# SDT_Neon_Predradnik.net
KiCad netlist of a schematic drawn in EAGLE
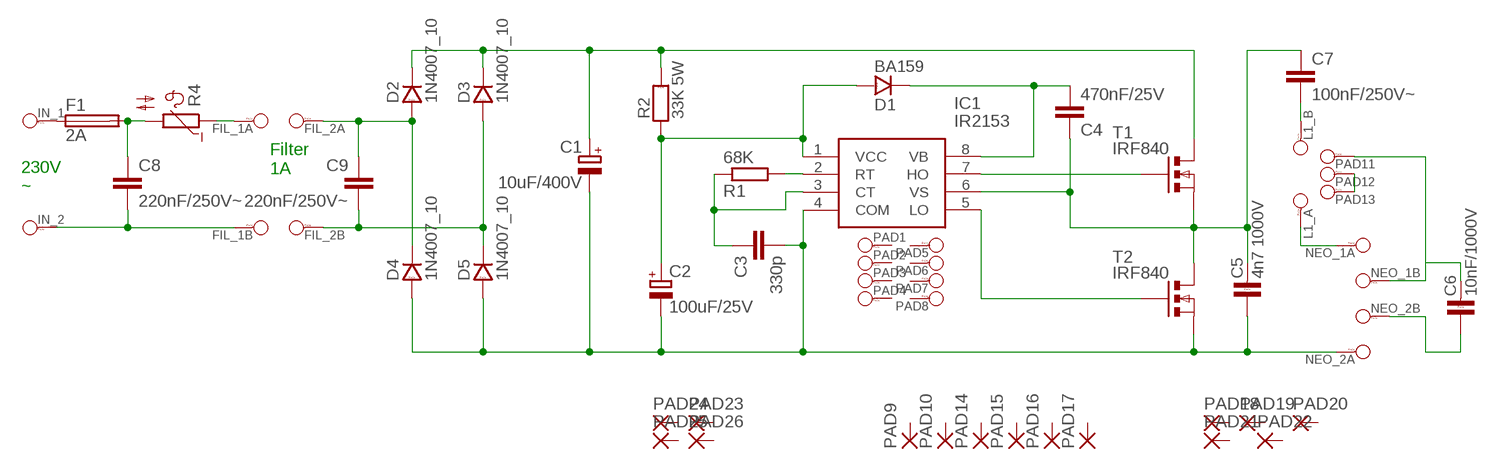
[diagram p0: schematic, sheet 1]

(export (version "E")
  (design (tool "Eeschema 10.0.6"))
  (components
    (comp (ref "C1")
      (value "10uF/400V")
      (footprint "eagle-import:ELEKTROLITICKY_RM5-10")
      (libsource (lib "eagle-import") (part "ELEKTROLITICKYRM5-10"))
    )
    (comp (ref "C2")
      (value "100uF/25V")
      (footprint "eagle-import:ELEKTROLITICKY_RM2,5-6,3")
      (libsource (lib "eagle-import") (part "ELEKTROLITICKYRM2,5-6,3"))
    )
    (comp (ref "C3")
      (value "330p")
      (footprint "eagle-import:KERAMICKY_RM5")
      (libsource (lib "eagle-import") (part "KERAMICKYRM5"))
    )
    (comp (ref "C4")
      (value "470nF/25V")
      (footprint "eagle-import:FOLIOVY_RM5_3,5-7,2")
      (libsource (lib "eagle-import") (part "FOLIOVYRM5/3,5-7,2"))
    )
    (comp (ref "C5")
      (value "4n7 1000V")
      (footprint "eagle-import:C-7,5")
      (libsource (lib "eagle-import") (part "C-KERAMIK_7,5"))
    )
    (comp (ref "C6")
      (value "10nF/1000V")
      (footprint "eagle-import:C-10")
      (libsource (lib "eagle-import") (part "C-KERAMIK_10"))
    )
    (comp (ref "C7")
      (value "100nF/250V~")
      (footprint "eagle-import:FOLIOVY_RM15_5-18")
      (libsource (lib "eagle-import") (part "FOLIOVYRM15/5-18"))
    )
    (comp (ref "C8")
      (value "220nF/250V~")
      (footprint "eagle-import:FOLIOVY_RM15_5-18")
      (libsource (lib "eagle-import") (part "FOLIOVYRM15/5-18"))
    )
    (comp (ref "C9")
      (value "220nF/250V~")
      (footprint "eagle-import:FOLIOVY_RM15_5-18")
      (libsource (lib "eagle-import") (part "FOLIOVYRM15/5-18"))
    )
    (comp (ref "D1")
      (value "BA159")
      (footprint "eagle-import:D-10")
      (libsource (lib "eagle-import") (part "BA159"))
    )
    (comp (ref "D2")
      (value "1N4007_10")
      (footprint "eagle-import:D-10")
      (libsource (lib "eagle-import") (part "1N4007_10"))
    )
    (comp (ref "D3")
      (value "1N4007_10")
      (footprint "eagle-import:D-10")
      (libsource (lib "eagle-import") (part "1N4007_10"))
    )
    (comp (ref "D4")
      (value "1N4007_10")
      (footprint "eagle-import:D-10")
      (libsource (lib "eagle-import") (part "1N4007_10"))
    )
    (comp (ref "D5")
      (value "1N4007_10")
      (footprint "eagle-import:D-10")
      (libsource (lib "eagle-import") (part "1N4007_10"))
    )
    (comp (ref "F1")
      (value "2A")
      (footprint "eagle-import:TE5")
      (libsource (lib "eagle-import") (part "FUSETE5"))
    )
    (comp (ref "FIL_1A")
      (value "PAD_1---")
      (footprint "eagle-import:PAD_1---")
      (libsource (lib "eagle-import") (part "PAD_1---"))
    )
    (comp (ref "FIL_1B")
      (value "PAD_1---")
      (footprint "eagle-import:PAD_1---")
      (libsource (lib "eagle-import") (part "PAD_1---"))
    )
    (comp (ref "FIL_2A")
      (value "PAD_1---")
      (footprint "eagle-import:PAD_1---")
      (libsource (lib "eagle-import") (part "PAD_1---"))
    )
    (comp (ref "FIL_2B")
      (value "PAD_1---")
      (footprint "eagle-import:PAD_1---")
      (libsource (lib "eagle-import") (part "PAD_1---"))
    )
    (comp (ref "IC1")
      (value "IR2153")
      (footprint "eagle-import:DIP762W56P254L988H533Q8N")
      (fields
        (field (name "MANUFACTURER_PART_NUMBER") "IR2153PBF")
        (field (name "MOUSER_PART_NUMBER") "942-IR2153PBF")
      )
      (libsource (lib "eagle-import") (part "IR2153PBF"))
    )
    (comp (ref "IN_1")
      (value "IN_~_1")
      (footprint "eagle-import:PAD_1---")
      (libsource (lib "eagle-import") (part "PAD_1---"))
    )
    (comp (ref "IN_2")
      (value "IN_~_1")
      (footprint "eagle-import:PAD_1---")
      (libsource (lib "eagle-import") (part "PAD_1---"))
    )
    (comp (ref "L1_A")
      (value "PAD_1---")
      (footprint "eagle-import:PAD_1---")
      (libsource (lib "eagle-import") (part "PAD_1---"))
    )
    (comp (ref "L1_B")
      (value "PAD_1---")
      (footprint "eagle-import:PAD_1---")
      (libsource (lib "eagle-import") (part "PAD_1---"))
    )
    (comp (ref "NEO_1A")
      (value "PAD_1---")
      (footprint "eagle-import:PAD_1---")
      (libsource (lib "eagle-import") (part "PAD_1---"))
    )
    (comp (ref "NEO_1B")
      (value "PAD_1---")
      (footprint "eagle-import:PAD_1---")
      (libsource (lib "eagle-import") (part "PAD_1---"))
    )
    (comp (ref "NEO_2A")
      (value "PAD_1---")
      (footprint "eagle-import:PAD_1---")
      (libsource (lib "eagle-import") (part "PAD_1---"))
    )
    (comp (ref "NEO_2B")
      (value "PAD_1---")
      (footprint "eagle-import:PAD_1---")
      (libsource (lib "eagle-import") (part "PAD_1---"))
    )
    (comp (ref "PAD1")
      (value "PAD_1---")
      (footprint "eagle-import:PAD_1---")
      (libsource (lib "eagle-import") (part "PAD_1---"))
    )
    (comp (ref "PAD2")
      (value "PAD_1---")
      (footprint "eagle-import:PAD_1---")
      (libsource (lib "eagle-import") (part "PAD_1---"))
    )
    (comp (ref "PAD3")
      (value "PAD_1---")
      (footprint "eagle-import:PAD_1---")
      (libsource (lib "eagle-import") (part "PAD_1---"))
    )
    (comp (ref "PAD4")
      (value "PAD_1---")
      (footprint "eagle-import:PAD_1---")
      (libsource (lib "eagle-import") (part "PAD_1---"))
    )
    (comp (ref "PAD5")
      (value "PAD_1---")
      (footprint "eagle-import:PAD_1---")
      (libsource (lib "eagle-import") (part "PAD_1---"))
    )
    (comp (ref "PAD6")
      (value "PAD_1---")
      (footprint "eagle-import:PAD_1---")
      (libsource (lib "eagle-import") (part "PAD_1---"))
    )
    (comp (ref "PAD7")
      (value "PAD_1---")
      (footprint "eagle-import:PAD_1---")
      (libsource (lib "eagle-import") (part "PAD_1---"))
    )
    (comp (ref "PAD8")
      (value "PAD_1---")
      (footprint "eagle-import:PAD_1---")
      (libsource (lib "eagle-import") (part "PAD_1---"))
    )
    (comp (ref "PAD9")
      (value "3,81/1,3")
      (footprint "eagle-import:3,81_1,3")
      (libsource (lib "eagle-import") (part "3,81/1,3"))
    )
    (comp (ref "PAD10")
      (value "3,81/1,3")
      (footprint "eagle-import:3,81_1,3")
      (libsource (lib "eagle-import") (part "3,81/1,3"))
    )
    (comp (ref "PAD11")
      (value "PAD_1---")
      (footprint "eagle-import:PAD_1---")
      (libsource (lib "eagle-import") (part "PAD_1---"))
    )
    (comp (ref "PAD12")
      (value "PAD_1---")
      (footprint "eagle-import:PAD_1---")
      (libsource (lib "eagle-import") (part "PAD_1---"))
    )
    (comp (ref "PAD13")
      (value "PAD_1---")
      (footprint "eagle-import:PAD_1---")
      (libsource (lib "eagle-import") (part "PAD_1---"))
    )
    (comp (ref "PAD14")
      (value "3,81/1,3")
      (footprint "eagle-import:3,81_1,3")
      (libsource (lib "eagle-import") (part "3,81/1,3"))
    )
    (comp (ref "PAD15")
      (value "3,81/1,3")
      (footprint "eagle-import:3,81_1,3")
      (libsource (lib "eagle-import") (part "3,81/1,3"))
    )
    (comp (ref "PAD16")
      (value "3,81/1,3")
      (footprint "eagle-import:3,81_1,3")
      (libsource (lib "eagle-import") (part "3,81/1,3"))
    )
    (comp (ref "PAD17")
      (value "3,81/1,3")
      (footprint "eagle-import:3,81_1,3")
      (libsource (lib "eagle-import") (part "3,81/1,3"))
    )
    (comp (ref "PAD18")
      (value "2,54/1,1")
      (footprint "eagle-import:2,54_1,1")
      (libsource (lib "eagle-import") (part "2,54/1,1"))
    )
    (comp (ref "PAD19")
      (value "2,54/1,1")
      (footprint "eagle-import:2,54_1,1")
      (libsource (lib "eagle-import") (part "2,54/1,1"))
    )
    (comp (ref "PAD20")
      (value "2,54/1,1")
      (footprint "eagle-import:2,54_1,1")
      (libsource (lib "eagle-import") (part "2,54/1,1"))
    )
    (comp (ref "PAD21")
      (value "2,54/1,1")
      (footprint "eagle-import:2,54_1,1")
      (libsource (lib "eagle-import") (part "2,54/1,1"))
    )
    (comp (ref "PAD22")
      (value "2,54/1,1")
      (footprint "eagle-import:2,54_1,1")
      (libsource (lib "eagle-import") (part "2,54/1,1"))
    )
    (comp (ref "PAD23")
      (value "2,54/1,1")
      (footprint "eagle-import:2,54_1,1")
      (libsource (lib "eagle-import") (part "2,54/1,1"))
    )
    (comp (ref "PAD24")
      (value "2,54/1,1")
      (footprint "eagle-import:2,54_1,1")
      (libsource (lib "eagle-import") (part "2,54/1,1"))
    )
    (comp (ref "PAD25")
      (value "2,54/1,1")
      (footprint "eagle-import:2,54_1,1")
      (libsource (lib "eagle-import") (part "2,54/1,1"))
    )
    (comp (ref "PAD26")
      (value "2,54/1,1")
      (footprint "eagle-import:2,54_1,1")
      (libsource (lib "eagle-import") (part "2,54/1,1"))
    )
    (comp (ref "R1")
      (value "68K")
      (footprint "eagle-import:0204_5")
      (libsource (lib "eagle-import") (part "R-EU_0204/5"))
    )
    (comp (ref "R2")
      (value "33K 5W")
      (footprint "eagle-import:R-_5W")
      (libsource (lib "eagle-import") (part "R__5W"))
    )
    (comp (ref "R4")
      (value "NTC644C")
      (footprint "eagle-import:N644C")
      (libsource (lib "eagle-import") (part "NTC644C"))
    )
    (comp (ref "T1")
      (value "IRF840")
      (footprint "eagle-import:TO-220S")
      (libsource (lib "eagle-import") (part "IRF840"))
    )
    (comp (ref "T2")
      (value "IRF840")
      (footprint "eagle-import:TO-220S")
      (libsource (lib "eagle-import") (part "IRF840"))
    )
  )
  (nets
    (net (code "1") (name "Net-(C1-+)") (class "Default")
      (node (ref "C1") (pin "P$2") (pinfunction "+_P$2") (pintype "passive"))
      (node (ref "D2") (pin "K") (pinfunction "K_K") (pintype "passive"))
      (node (ref "D3") (pin "K") (pinfunction "K_K") (pintype "passive"))
      (node (ref "R2") (pin "2") (pinfunction "2_2") (pintype "passive"))
      (node (ref "T1") (pin "2") (pinfunction "D_2") (pintype "passive"))
    )
    (net (code "2") (name "Net-(C1--)") (class "Default")
      (node (ref "C1") (pin "P$1") (pinfunction "-_P$1") (pintype "passive"))
      (node (ref "C2") (pin "P$1") (pinfunction "-_P$1") (pintype "passive"))
      (node (ref "C3") (pin "P$2") (pinfunction "2_P$2") (pintype "passive"))
      (node (ref "C5") (pin "1") (pinfunction "1_1") (pintype "passive"))
      (node (ref "D4") (pin "A") (pinfunction "A_A") (pintype "passive"))
      (node (ref "D5") (pin "A") (pinfunction "A_A") (pintype "passive"))
      (node (ref "IC1") (pin "4") (pinfunction "COM_4") (pintype "bidirectional"))
      (node (ref "NEO_2A") (pin "1") (pinfunction "1_1") (pintype "passive"))
      (node (ref "T2") (pin "3") (pinfunction "S_3") (pintype "passive"))
    )
    (net (code "3") (name "Net-(C2-+)") (class "Default")
      (node (ref "C2") (pin "P$2") (pinfunction "+_P$2") (pintype "passive"))
      (node (ref "D1") (pin "A") (pinfunction "A_A") (pintype "passive"))
      (node (ref "IC1") (pin "1") (pinfunction "VCC_1") (pintype "bidirectional"))
      (node (ref "R2") (pin "1") (pinfunction "1_1") (pintype "passive"))
    )
    (net (code "4") (name "Net-(C3-1)") (class "Default")
      (node (ref "C3") (pin "P$1") (pinfunction "1_P$1") (pintype "passive"))
      (node (ref "IC1") (pin "3") (pinfunction "CT_3") (pintype "bidirectional"))
      (node (ref "R1") (pin "1") (pinfunction "1_1") (pintype "passive"))
    )
    (net (code "5") (name "Net-(C4-1)") (class "Default")
      (node (ref "C4") (pin "P$1") (pinfunction "1_P$1") (pintype "passive"))
      (node (ref "C5") (pin "2") (pinfunction "2_2") (pintype "passive"))
      (node (ref "C7") (pin "P$1") (pinfunction "1_P$1") (pintype "passive"))
      (node (ref "IC1") (pin "6") (pinfunction "VS_6") (pintype "bidirectional"))
      (node (ref "T1") (pin "3") (pinfunction "S_3") (pintype "passive"))
      (node (ref "T2") (pin "2") (pinfunction "D_2") (pintype "passive"))
    )
    (net (code "6") (name "Net-(C4-2)") (class "Default")
      (node (ref "C4") (pin "P$2") (pinfunction "2_P$2") (pintype "passive"))
      (node (ref "D1") (pin "K") (pinfunction "K_K") (pintype "passive"))
      (node (ref "IC1") (pin "8") (pinfunction "VB_8") (pintype "bidirectional"))
    )
    (net (code "7") (name "Net-(C6-Pad1)") (class "Default")
      (node (ref "C6") (pin "1") (pinfunction "1_1") (pintype "passive"))
      (node (ref "NEO_2B") (pin "1") (pinfunction "1_1") (pintype "passive"))
    )
    (net (code "8") (name "Net-(C6-Pad2)") (class "Default")
      (node (ref "C6") (pin "2") (pinfunction "2_2") (pintype "passive"))
      (node (ref "NEO_1B") (pin "1") (pinfunction "1_1") (pintype "passive"))
      (node (ref "PAD11") (pin "1") (pinfunction "1_1") (pintype "passive"))
    )
    (net (code "9") (name "Net-(C7-2)") (class "Default")
      (node (ref "C7") (pin "P$2") (pinfunction "2_P$2") (pintype "passive"))
      (node (ref "L1_B") (pin "1") (pinfunction "1_1") (pintype "passive"))
    )
    (net (code "10") (name "Net-(C8-1)") (class "Default")
      (node (ref "C8") (pin "P$1") (pinfunction "1_P$1") (pintype "passive"))
      (node (ref "F1") (pin "2") (pinfunction "2_2") (pintype "passive"))
      (node (ref "R4") (pin "2") (pinfunction "2_2") (pintype "passive"))
    )
    (net (code "11") (name "Net-(C8-2)") (class "Default")
      (node (ref "C8") (pin "P$2") (pinfunction "2_P$2") (pintype "passive"))
      (node (ref "FIL_1B") (pin "1") (pinfunction "1_1") (pintype "passive"))
      (node (ref "IN_2") (pin "1") (pinfunction "1_1") (pintype "passive"))
    )
    (net (code "12") (name "Net-(C9-1)") (class "Default")
      (node (ref "C9") (pin "P$1") (pinfunction "1_P$1") (pintype "passive"))
      (node (ref "D2") (pin "A") (pinfunction "A_A") (pintype "passive"))
      (node (ref "D4") (pin "K") (pinfunction "K_K") (pintype "passive"))
      (node (ref "FIL_2A") (pin "1") (pinfunction "1_1") (pintype "passive"))
    )
    (net (code "13") (name "Net-(C9-2)") (class "Default")
      (node (ref "C9") (pin "P$2") (pinfunction "2_P$2") (pintype "passive"))
      (node (ref "D3") (pin "A") (pinfunction "A_A") (pintype "passive"))
      (node (ref "D5") (pin "K") (pinfunction "K_K") (pintype "passive"))
      (node (ref "FIL_2B") (pin "1") (pinfunction "1_1") (pintype "passive"))
    )
    (net (code "14") (name "Net-(F1-Pad1)") (class "Default")
      (node (ref "F1") (pin "1") (pinfunction "1_1") (pintype "passive"))
      (node (ref "IN_1") (pin "1") (pinfunction "1_1") (pintype "passive"))
    )
    (net (code "15") (name "Net-(FIL_1A-Pad1)") (class "Default")
      (node (ref "FIL_1A") (pin "1") (pinfunction "1_1") (pintype "passive"))
      (node (ref "R4") (pin "1") (pinfunction "1_1") (pintype "passive"))
    )
    (net (code "16") (name "Net-(IC1-HO)") (class "Default")
      (node (ref "IC1") (pin "7") (pinfunction "HO_7") (pintype "bidirectional"))
      (node (ref "T1") (pin "1") (pinfunction "G_1") (pintype "passive"))
    )
    (net (code "17") (name "Net-(IC1-LO)") (class "Default")
      (node (ref "IC1") (pin "5") (pinfunction "LO_5") (pintype "bidirectional"))
      (node (ref "T2") (pin "1") (pinfunction "G_1") (pintype "passive"))
    )
    (net (code "18") (name "Net-(IC1-RT)") (class "Default")
      (node (ref "IC1") (pin "2") (pinfunction "RT_2") (pintype "bidirectional"))
      (node (ref "R1") (pin "2") (pinfunction "2_2") (pintype "passive"))
    )
    (net (code "19") (name "Net-(L1_A-Pad1)") (class "Default")
      (node (ref "L1_A") (pin "1") (pinfunction "1_1") (pintype "passive"))
      (node (ref "NEO_1A") (pin "1") (pinfunction "1_1") (pintype "passive"))
    )
    (net (code "20") (name "Net-(PAD12-Pad1)") (class "Default")
      (node (ref "PAD12") (pin "1") (pinfunction "1_1") (pintype "passive"))
      (node (ref "PAD13") (pin "1") (pinfunction "1_1") (pintype "passive"))
    )
    (net (code "21") (name "unconnected-(PAD1-Pad1)") (class "Default")
      (node (ref "PAD1") (pin "1") (pinfunction "1_1") (pintype "passive"))
    )
    (net (code "22") (name "unconnected-(PAD2-Pad1)") (class "Default")
      (node (ref "PAD2") (pin "1") (pinfunction "1_1") (pintype "passive"))
    )
    (net (code "23") (name "unconnected-(PAD3-Pad1)") (class "Default")
      (node (ref "PAD3") (pin "1") (pinfunction "1_1") (pintype "passive"))
    )
    (net (code "24") (name "unconnected-(PAD4-Pad1)") (class "Default")
      (node (ref "PAD4") (pin "1") (pinfunction "1_1") (pintype "passive"))
    )
    (net (code "25") (name "unconnected-(PAD5-Pad1)") (class "Default")
      (node (ref "PAD5") (pin "1") (pinfunction "1_1") (pintype "passive"))
    )
    (net (code "26") (name "unconnected-(PAD6-Pad1)") (class "Default")
      (node (ref "PAD6") (pin "1") (pinfunction "1_1") (pintype "passive"))
    )
    (net (code "27") (name "unconnected-(PAD7-Pad1)") (class "Default")
      (node (ref "PAD7") (pin "1") (pinfunction "1_1") (pintype "passive"))
    )
    (net (code "28") (name "unconnected-(PAD8-Pad1)") (class "Default")
      (node (ref "PAD8") (pin "1") (pinfunction "1_1") (pintype "passive"))
    )
    (net (code "29") (name "unconnected-(PAD9-P-Pad1)") (class "Default")
      (node (ref "PAD9") (pin "1") (pinfunction "P_1") (pintype "passive"))
    )
    (net (code "30") (name "unconnected-(PAD10-P-Pad1)") (class "Default")
      (node (ref "PAD10") (pin "1") (pinfunction "P_1") (pintype "passive"))
    )
    (net (code "31") (name "unconnected-(PAD14-P-Pad1)") (class "Default")
      (node (ref "PAD14") (pin "1") (pinfunction "P_1") (pintype "passive"))
    )
    (net (code "32") (name "unconnected-(PAD15-P-Pad1)") (class "Default")
      (node (ref "PAD15") (pin "1") (pinfunction "P_1") (pintype "passive"))
    )
    (net (code "33") (name "unconnected-(PAD16-P-Pad1)") (class "Default")
      (node (ref "PAD16") (pin "1") (pinfunction "P_1") (pintype "passive"))
    )
    (net (code "34") (name "unconnected-(PAD17-P-Pad1)") (class "Default")
      (node (ref "PAD17") (pin "1") (pinfunction "P_1") (pintype "passive"))
    )
    (net (code "35") (name "unconnected-(PAD18-P-Pad1)") (class "Default")
      (node (ref "PAD18") (pin "1") (pinfunction "P_1") (pintype "passive"))
    )
    (net (code "36") (name "unconnected-(PAD19-P-Pad1)") (class "Default")
      (node (ref "PAD19") (pin "1") (pinfunction "P_1") (pintype "passive"))
    )
    (net (code "37") (name "unconnected-(PAD20-P-Pad1)") (class "Default")
      (node (ref "PAD20") (pin "1") (pinfunction "P_1") (pintype "passive"))
    )
    (net (code "38") (name "unconnected-(PAD21-P-Pad1)") (class "Default")
      (node (ref "PAD21") (pin "1") (pinfunction "P_1") (pintype "passive"))
    )
    (net (code "39") (name "unconnected-(PAD22-P-Pad1)") (class "Default")
      (node (ref "PAD22") (pin "1") (pinfunction "P_1") (pintype "passive"))
    )
    (net (code "40") (name "unconnected-(PAD23-P-Pad1)") (class "Default")
      (node (ref "PAD23") (pin "1") (pinfunction "P_1") (pintype "passive"))
    )
    (net (code "41") (name "unconnected-(PAD24-P-Pad1)") (class "Default")
      (node (ref "PAD24") (pin "1") (pinfunction "P_1") (pintype "passive"))
    )
    (net (code "42") (name "unconnected-(PAD25-P-Pad1)") (class "Default")
      (node (ref "PAD25") (pin "1") (pinfunction "P_1") (pintype "passive"))
    )
    (net (code "43") (name "unconnected-(PAD26-P-Pad1)") (class "Default")
      (node (ref "PAD26") (pin "1") (pinfunction "P_1") (pintype "passive"))
    )
  )
)
